# Sheet1.net
KiCad netlist of a schematic drawn in Altium Designer
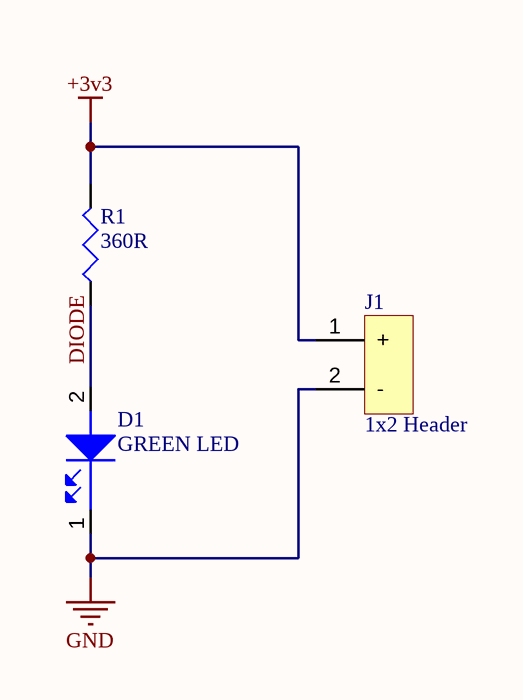
[diagram p0: Sheet1.SchDoc]

(export (version "E")
  (design (tool "Eeschema 10.0.6"))
  (components
    (comp (ref "D1")
      (value "GREEN LED")
      (footprint "LED0603G")
      (description "LED GREEN 0603 SMD")
      (fields
        (field (name "MANUFACTURER") "Panasonic SSG")
        (field (name "MANUFACTURER PART NUMBER") "LNJ337W83RA")
      )
      (libsource (lib "LED_Schlib") (part "LNJ337W83RA"))
    )
    (comp (ref "J1")
      (value "1x2 Header")
      (footprint "HEADER1x2")
      (description "KK 254 Wire-to-Board Header, Vertical, with Friction Lock, 2 Circuits, Gold (Au) Plating")
      (fields (field (name "MANUFACTURER") "Molex") (field (name "MANUFACTURER PART NUMBER") "22-29-2021"))
      (libsource (lib "LED_Schlib") (part "22-29-2021"))
    )
    (comp (ref "R1")
      (value "360R")
      (footprint "R0805")
      (description "Res Thick Film 0805 360 Ohm 1% 1/8W ±100ppm/°C Molded SMD SMD Paper T/R")
      (fields
        (field (name "MANUFACTURER") "Vishay")
        (field (name "MANUFACTURER PART NUMBER") "CRCW0805360RFKEA")
      )
      (libsource (lib "LED_Schlib") (part "CRCW0805360RFKEA"))
    )
  )
  (nets
    (net (code "1") (name "+3v3") (class "Default")
      (node (ref "J1") (pin "1") (pinfunction "+_1") (pintype "passive"))
      (node (ref "R1") (pin "2") (pinfunction "2_2") (pintype "passive"))
    )
    (net (code "2") (name "/DIODE") (class "Default")
      (node (ref "D1") (pin "2") (pinfunction "2_2") (pintype "passive"))
      (node (ref "R1") (pin "1") (pinfunction "1_1") (pintype "passive"))
    )
    (net (code "3") (name "GND") (class "Default")
      (node (ref "D1") (pin "1") (pinfunction "1_1") (pintype "passive"))
      (node (ref "J1") (pin "2") (pinfunction "-_2") (pintype "passive"))
    )
  )
)
